# Core.net
KiCad netlist of a schematic drawn in Altium Designer
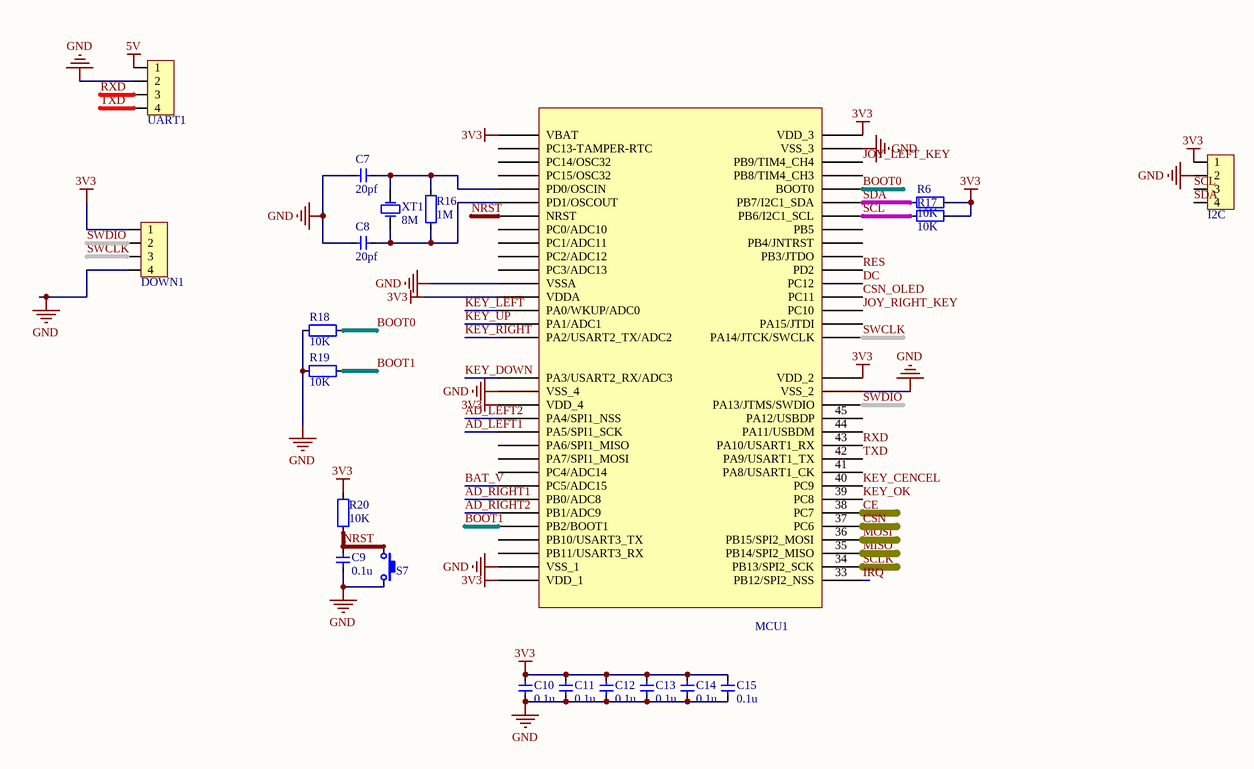
[diagram p0: Core.SchDoc]

(export (version "E")
  (design (tool "Eeschema 10.0.6"))
  (components
    (comp (ref "C7")
      (value "20pf")
      (footprint "PCB_PassiveCap:CAP_0603")
      (description "Capacitor")
      (fields (field (name "Comment") "Cap_0603"))
      (libsource (lib "SCH_Passive") (part "Cap_0603"))
    )
    (comp (ref "C8")
      (value "20pf")
      (footprint "PCB_PassiveCap:CAP_0603")
      (description "Capacitor")
      (fields (field (name "Comment") "Cap_0603"))
      (libsource (lib "SCH_Passive") (part "Cap_0603"))
    )
    (comp (ref "C9")
      (value "0.1u")
      (footprint "PCB_PassiveCap:CAP_0603")
      (description "Capacitor")
      (fields (field (name "Comment") "Cap_0603"))
      (libsource (lib "SCH_Passive") (part "Cap_0603"))
    )
    (comp (ref "C10")
      (value "0.1u")
      (footprint "PCB_PassiveCap:CAP_0603")
      (description "Capacitor")
      (fields (field (name "Comment") "Cap_0603"))
      (libsource (lib "SCH_Passive") (part "Cap_0603"))
    )
    (comp (ref "C11")
      (value "0.1u")
      (footprint "PCB_PassiveCap:CAP_0603")
      (description "Capacitor")
      (fields (field (name "Comment") "Cap_0603"))
      (libsource (lib "SCH_Passive") (part "Cap_0603"))
    )
    (comp (ref "C12")
      (value "0.1u")
      (footprint "PCB_PassiveCap:CAP_0603")
      (description "Capacitor")
      (fields (field (name "Comment") "Cap_0603"))
      (libsource (lib "SCH_Passive") (part "Cap_0603"))
    )
    (comp (ref "C13")
      (value "0.1u")
      (footprint "PCB_PassiveCap:CAP_0603")
      (description "Capacitor")
      (fields (field (name "Comment") "Cap_0603"))
      (libsource (lib "SCH_Passive") (part "Cap_0603"))
    )
    (comp (ref "C14")
      (value "0.1u")
      (footprint "PCB_PassiveCap:CAP_0603")
      (description "Capacitor")
      (fields (field (name "Comment") "Cap_0603"))
      (libsource (lib "SCH_Passive") (part "Cap_0603"))
    )
    (comp (ref "C15")
      (value "0.1u")
      (footprint "PCB_PassiveCap:CAP_0603")
      (description "Capacitor")
      (fields (field (name "Comment") "Cap_0603"))
      (libsource (lib "SCH_Passive") (part "Cap_0603"))
    )
    (comp (ref "DOWN1")
      (value "HDR1x4_2.54")
      (footprint "PCB_ConnectorHDR:HDR1x4_2.54_180")
      (description "Header")
      (libsource (lib "SCH_ConnectorHDR") (part "HDR1x4_2.54"))
    )
    (comp (ref "I2C")
      (value "HDR1x4_2.54")
      (footprint "PCB_ConnectorHDR:HDR1x4_2.54_180")
      (description "Header")
      (libsource (lib "SCH_ConnectorHDR") (part "HDR1x4_2.54"))
    )
    (comp (ref "MCU1")
      (value "STM32F103RC")
      (footprint "LQFP_P0.5_64")
      (description "MCU")
      (libsource (lib "SCH_IntegratedCircuit") (part "STM32F103RC"))
    )
    (comp (ref "R6")
      (value "10K")
      (footprint "PCB_PassiveRes:RES_0603")
      (description "Resistor")
      (fields (field (name "Comment") "Res_0603"))
      (libsource (lib "") (part "Res_0603_1"))
    )
    (comp (ref "R16")
      (value "1M")
      (footprint "PCB_PassiveRes:RES_0603")
      (description "Resistor")
      (fields (field (name "Comment") "Res_0603"))
      (libsource (lib "") (part "Res_0603_3"))
    )
    (comp (ref "R17")
      (value "10K")
      (footprint "PCB_PassiveRes:RES_0603")
      (description "Resistor")
      (fields (field (name "Comment") "Res_0603"))
      (libsource (lib "") (part "Res_0603_1"))
    )
    (comp (ref "R18")
      (value "10K")
      (footprint "PCB_PassiveRes:RES_0603")
      (description "Resistor")
      (fields (field (name "Comment") "Res_0603"))
      (libsource (lib "") (part "Res_0603_2"))
    )
    (comp (ref "R19")
      (value "10K")
      (footprint "PCB_PassiveRes:RES_0603")
      (description "Resistor")
      (fields (field (name "Comment") "Res_0603"))
      (libsource (lib "") (part "Res_0603_2"))
    )
    (comp (ref "R20")
      (value "10K")
      (footprint "PCB_PassiveRes:RES_0603")
      (description "Resistor")
      (fields (field (name "Comment") "Res_0603"))
      (libsource (lib "SCH_Passive") (part "Res_0603"))
    )
    (comp (ref "S7")
      (value "ButtonTACT_3x4x2_180")
      (footprint "PCB_Switch:ButtonTACT_3x4x2_180H")
      (description "Button")
      (libsource (lib "SCH_Switch") (part "ButtonTACT_3x4x2_180"))
    )
    (comp (ref "UART1")
      (value "HDR1x4_2.54")
      (footprint "PCB_ConnectorHDR:HDR1x4_2.54_180")
      (description "Header")
      (libsource (lib "SCH_ConnectorHDR") (part "HDR1x4_2.54"))
    )
    (comp (ref "XT1")
      (value "8M")
      (footprint "PCB_Oscillator:XT_5032_2")
      (description "Crystal Oscillator")
      (fields (field (name "Comment") "XTAL_5032_2P"))
      (libsource (lib "SCH_Oscillator") (part "XTAL_5032_2P"))
    )
  )
  (nets
    (net (code "1") (name "/AD_LEFT1") (class "Default")
      (node (ref "MCU1") (pin "21") (pinfunction "PA5/SPI1_SCK_21") (pintype "passive"))
    )
    (net (code "2") (name "/AD_LEFT2") (class "Default")
      (node (ref "MCU1") (pin "20") (pinfunction "PA4/SPI1_NSS_20") (pintype "passive"))
    )
    (net (code "3") (name "/AD_RIGHT1") (class "Default")
      (node (ref "MCU1") (pin "26") (pinfunction "PB0/ADC8_26") (pintype "passive"))
    )
    (net (code "4") (name "/AD_RIGHT2") (class "Default")
      (node (ref "MCU1") (pin "27") (pinfunction "PB1/ADC9_27") (pintype "passive"))
    )
    (net (code "5") (name "/BAT_V") (class "Default")
      (node (ref "MCU1") (pin "25") (pinfunction "PC5/ADC15_25") (pintype "passive"))
    )
    (net (code "6") (name "/BOOT0") (class "Default")
      (node (ref "MCU1") (pin "60") (pinfunction "BOOT0_60") (pintype "passive"))
      (node (ref "R18") (pin "1") (pinfunction "1_1") (pintype "passive"))
    )
    (net (code "7") (name "/BOOT1") (class "Default")
      (node (ref "MCU1") (pin "28") (pinfunction "PB2/BOOT1_28") (pintype "passive"))
      (node (ref "R19") (pin "1") (pinfunction "1_1") (pintype "passive"))
    )
    (net (code "8") (name "/CE") (class "Default")
      (node (ref "MCU1") (pin "38") (pinfunction "PC7_38") (pintype "passive"))
    )
    (net (code "9") (name "/CSN") (class "Default")
      (node (ref "MCU1") (pin "37") (pinfunction "PC6_37") (pintype "passive"))
    )
    (net (code "10") (name "/CSN_OLED") (class "Default")
      (node (ref "MCU1") (pin "52") (pinfunction "PC11_52") (pintype "passive"))
    )
    (net (code "11") (name "/DC") (class "Default")
      (node (ref "MCU1") (pin "53") (pinfunction "PC12_53") (pintype "passive"))
    )
    (net (code "12") (name "/IRQ") (class "Default")
      (node (ref "MCU1") (pin "33") (pinfunction "PB12/SPI2_NSS_33") (pintype "passive"))
    )
    (net (code "13") (name "/JOY_LEFT_KEY") (class "Default")
      (node (ref "MCU1") (pin "62") (pinfunction "PB9/TIM4_CH4_62") (pintype "passive"))
    )
    (net (code "14") (name "/JOY_RIGHT_KEY") (class "Default")
      (node (ref "MCU1") (pin "51") (pinfunction "PC10_51") (pintype "passive"))
    )
    (net (code "15") (name "/KEY_CENCEL") (class "Default")
      (node (ref "MCU1") (pin "40") (pinfunction "PC9_40") (pintype "passive"))
    )
    (net (code "16") (name "/KEY_DOWN") (class "Default")
      (node (ref "MCU1") (pin "17") (pinfunction "PA3/USART2_RX/ADC3_17") (pintype "passive"))
    )
    (net (code "17") (name "/KEY_LEFT") (class "Default")
      (node (ref "MCU1") (pin "14") (pinfunction "PA0/WKUP/ADC0_14") (pintype "passive"))
    )
    (net (code "18") (name "/KEY_OK") (class "Default")
      (node (ref "MCU1") (pin "39") (pinfunction "PC8_39") (pintype "passive"))
    )
    (net (code "19") (name "/KEY_RIGHT") (class "Default")
      (node (ref "MCU1") (pin "16") (pinfunction "PA2/USART2_TX/ADC2_16") (pintype "passive"))
    )
    (net (code "20") (name "/KEY_UP") (class "Default")
      (node (ref "MCU1") (pin "15") (pinfunction "PA1/ADC1_15") (pintype "passive"))
    )
    (net (code "21") (name "/MISO") (class "Default")
      (node (ref "MCU1") (pin "35") (pinfunction "PB14/SPI2_MISO_35") (pintype "passive"))
    )
    (net (code "22") (name "/MOSI") (class "Default")
      (node (ref "MCU1") (pin "36") (pinfunction "PB15/SPI2_MOSI_36") (pintype "passive"))
    )
    (net (code "23") (name "/NRST") (class "Default")
      (node (ref "C9") (pin "2") (pinfunction "2_2") (pintype "passive"))
      (node (ref "MCU1") (pin "7") (pinfunction "NRST_7") (pintype "passive"))
      (node (ref "R20") (pin "2") (pinfunction "2_2") (pintype "passive"))
      (node (ref "S7") (pin "1") (pinfunction "1_1") (pintype "passive"))
    )
    (net (code "24") (name "/RES") (class "Default")
      (node (ref "MCU1") (pin "54") (pinfunction "PD2_54") (pintype "passive"))
    )
    (net (code "25") (name "/RXD") (class "Default")
      (node (ref "MCU1") (pin "43") (pinfunction "PA10/USART1_RX_43") (pintype "passive"))
      (node (ref "UART1") (pin "3") (pinfunction "3_3") (pintype "passive"))
    )
    (net (code "26") (name "/SCL") (class "Default")
      (node (ref "I2C") (pin "3") (pinfunction "3_3") (pintype "passive"))
      (node (ref "MCU1") (pin "58") (pinfunction "PB6/I2C1_SCL_58") (pintype "passive"))
      (node (ref "R17") (pin "1") (pinfunction "1_1") (pintype "passive"))
    )
    (net (code "27") (name "/SCLK") (class "Default")
      (node (ref "MCU1") (pin "34") (pinfunction "PB13/SPI2_SCK_34") (pintype "passive"))
    )
    (net (code "28") (name "/SDA") (class "Default")
      (node (ref "I2C") (pin "4") (pinfunction "4_4") (pintype "passive"))
      (node (ref "MCU1") (pin "59") (pinfunction "PB7/I2C1_SDA_59") (pintype "passive"))
      (node (ref "R6") (pin "1") (pinfunction "1_1") (pintype "passive"))
    )
    (net (code "29") (name "/SWCLK") (class "Default")
      (node (ref "DOWN1") (pin "3") (pinfunction "3_3") (pintype "passive"))
      (node (ref "MCU1") (pin "49") (pinfunction "PA14/JTCK/SWCLK_49") (pintype "passive"))
    )
    (net (code "30") (name "/SWDIO") (class "Default")
      (node (ref "DOWN1") (pin "2") (pinfunction "2_2") (pintype "passive"))
      (node (ref "MCU1") (pin "46") (pinfunction "PA13/JTMS/SWDIO_46") (pintype "passive"))
    )
    (net (code "31") (name "/TXD") (class "Default")
      (node (ref "MCU1") (pin "42") (pinfunction "PA9/USART1_TX_42") (pintype "passive"))
      (node (ref "UART1") (pin "4") (pinfunction "4_4") (pintype "passive"))
    )
    (net (code "32") (name "3V3") (class "Default")
      (node (ref "C10") (pin "2") (pinfunction "2_2") (pintype "passive"))
      (node (ref "C11") (pin "2") (pinfunction "2_2") (pintype "passive"))
      (node (ref "C12") (pin "2") (pinfunction "2_2") (pintype "passive"))
      (node (ref "C13") (pin "2") (pinfunction "2_2") (pintype "passive"))
      (node (ref "C14") (pin "2") (pinfunction "2_2") (pintype "passive"))
      (node (ref "C15") (pin "2") (pinfunction "2_2") (pintype "passive"))
      (node (ref "DOWN1") (pin "1") (pinfunction "1_1") (pintype "passive"))
      (node (ref "I2C") (pin "1") (pinfunction "1_1") (pintype "passive"))
      (node (ref "MCU1") (pin "1") (pinfunction "VBAT_1") (pintype "passive"))
      (node (ref "MCU1") (pin "13") (pinfunction "VDDA_13") (pintype "passive"))
      (node (ref "MCU1") (pin "19") (pinfunction "VDD_4_19") (pintype "passive"))
      (node (ref "MCU1") (pin "32") (pinfunction "VDD_1_32") (pintype "passive"))
      (node (ref "MCU1") (pin "48") (pinfunction "VDD_2_48") (pintype "passive"))
      (node (ref "MCU1") (pin "64") (pinfunction "VDD_3_64") (pintype "passive"))
      (node (ref "R17") (pin "2") (pinfunction "2_2") (pintype "passive"))
      (node (ref "R20") (pin "1") (pinfunction "1_1") (pintype "passive"))
      (node (ref "R6") (pin "2") (pinfunction "2_2") (pintype "passive"))
    )
    (net (code "33") (name "5V") (class "Default")
      (node (ref "UART1") (pin "1") (pinfunction "1_1") (pintype "passive"))
    )
    (net (code "34") (name "GND") (class "Default")
      (node (ref "C10") (pin "1") (pinfunction "1_1") (pintype "passive"))
      (node (ref "C11") (pin "1") (pinfunction "1_1") (pintype "passive"))
      (node (ref "C12") (pin "1") (pinfunction "1_1") (pintype "passive"))
      (node (ref "C13") (pin "1") (pinfunction "1_1") (pintype "passive"))
      (node (ref "C14") (pin "1") (pinfunction "1_1") (pintype "passive"))
      (node (ref "C15") (pin "1") (pinfunction "1_1") (pintype "passive"))
      (node (ref "C7") (pin "1") (pinfunction "1_1") (pintype "passive"))
      (node (ref "C8") (pin "1") (pinfunction "1_1") (pintype "passive"))
      (node (ref "C9") (pin "1") (pinfunction "1_1") (pintype "passive"))
      (node (ref "DOWN1") (pin "4") (pinfunction "4_4") (pintype "passive"))
      (node (ref "I2C") (pin "2") (pinfunction "2_2") (pintype "passive"))
      (node (ref "MCU1") (pin "12") (pinfunction "VSSA_12") (pintype "passive"))
      (node (ref "MCU1") (pin "18") (pinfunction "VSS_4_18") (pintype "passive"))
      (node (ref "MCU1") (pin "31") (pinfunction "VSS_1_31") (pintype "passive"))
      (node (ref "MCU1") (pin "47") (pinfunction "VSS_2_47") (pintype "passive"))
      (node (ref "MCU1") (pin "63") (pinfunction "VSS_3_63") (pintype "passive"))
      (node (ref "R18") (pin "2") (pinfunction "2_2") (pintype "passive"))
      (node (ref "R19") (pin "2") (pinfunction "2_2") (pintype "passive"))
      (node (ref "S7") (pin "2") (pinfunction "2_2") (pintype "passive"))
      (node (ref "UART1") (pin "2") (pinfunction "2_2") (pintype "passive"))
    )
    (net (code "35") (name "Net-(MCU1-PD0{slash}OSCIN)") (class "Default")
      (node (ref "C7") (pin "2") (pinfunction "2_2") (pintype "passive"))
      (node (ref "MCU1") (pin "5") (pinfunction "PD0/OSCIN_5") (pintype "passive"))
      (node (ref "R16") (pin "2") (pinfunction "2_2") (pintype "passive"))
      (node (ref "XT1") (pin "2") (pinfunction "OSC2_2") (pintype "passive"))
    )
    (net (code "36") (name "Net-(MCU1-PD1{slash}OSCOUT)") (class "Default")
      (node (ref "C8") (pin "2") (pinfunction "2_2") (pintype "passive"))
      (node (ref "MCU1") (pin "6") (pinfunction "PD1/OSCOUT_6") (pintype "passive"))
      (node (ref "R16") (pin "1") (pinfunction "1_1") (pintype "passive"))
      (node (ref "XT1") (pin "1") (pinfunction "OSC1_1") (pintype "passive"))
    )
    (net (code "37") (name "unconnected-(MCU1-PA6{slash}SPI1_MISO-Pad22)") (class "Default")
      (node (ref "MCU1") (pin "22") (pinfunction "PA6/SPI1_MISO_22") (pintype "passive"))
    )
    (net (code "38") (name "unconnected-(MCU1-PA7{slash}SPI1_MOSI-Pad23)") (class "Default")
      (node (ref "MCU1") (pin "23") (pinfunction "PA7/SPI1_MOSI_23") (pintype "passive"))
    )
    (net (code "39") (name "unconnected-(MCU1-PA8{slash}USART1_CK-Pad41)") (class "Default")
      (node (ref "MCU1") (pin "41") (pinfunction "PA8/USART1_CK_41") (pintype "passive"))
    )
    (net (code "40") (name "unconnected-(MCU1-PA11{slash}USBDM-Pad44)") (class "Default")
      (node (ref "MCU1") (pin "44") (pinfunction "PA11/USBDM_44") (pintype "passive"))
    )
    (net (code "41") (name "unconnected-(MCU1-PA12{slash}USBDP-Pad45)") (class "Default")
      (node (ref "MCU1") (pin "45") (pinfunction "PA12/USBDP_45") (pintype "passive"))
    )
    (net (code "42") (name "unconnected-(MCU1-PA15{slash}JTDI-Pad50)") (class "Default")
      (node (ref "MCU1") (pin "50") (pinfunction "PA15/JTDI_50") (pintype "passive"))
    )
    (net (code "43") (name "unconnected-(MCU1-PB3{slash}JTDO-Pad55)") (class "Default")
      (node (ref "MCU1") (pin "55") (pinfunction "PB3/JTDO_55") (pintype "passive"))
    )
    (net (code "44") (name "unconnected-(MCU1-PB4{slash}JNTRST-Pad56)") (class "Default")
      (node (ref "MCU1") (pin "56") (pinfunction "PB4/JNTRST_56") (pintype "passive"))
    )
    (net (code "45") (name "unconnected-(MCU1-PB5-Pad57)") (class "Default")
      (node (ref "MCU1") (pin "57") (pinfunction "PB5_57") (pintype "passive"))
    )
    (net (code "46") (name "unconnected-(MCU1-PB8{slash}TIM4_CH3-Pad61)") (class "Default")
      (node (ref "MCU1") (pin "61") (pinfunction "PB8/TIM4_CH3_61") (pintype "passive"))
    )
    (net (code "47") (name "unconnected-(MCU1-PB10{slash}USART3_TX-Pad29)") (class "Default")
      (node (ref "MCU1") (pin "29") (pinfunction "PB10/USART3_TX_29") (pintype "passive"))
    )
    (net (code "48") (name "unconnected-(MCU1-PB11{slash}USART3_RX-Pad30)") (class "Default")
      (node (ref "MCU1") (pin "30") (pinfunction "PB11/USART3_RX_30") (pintype "passive"))
    )
    (net (code "49") (name "unconnected-(MCU1-PC0{slash}ADC10-Pad8)") (class "Default")
      (node (ref "MCU1") (pin "8") (pinfunction "PC0/ADC10_8") (pintype "passive"))
    )
    (net (code "50") (name "unconnected-(MCU1-PC1{slash}ADC11-Pad9)") (class "Default")
      (node (ref "MCU1") (pin "9") (pinfunction "PC1/ADC11_9") (pintype "passive"))
    )
    (net (code "51") (name "unconnected-(MCU1-PC2{slash}ADC12-Pad10)") (class "Default")
      (node (ref "MCU1") (pin "10") (pinfunction "PC2/ADC12_10") (pintype "passive"))
    )
    (net (code "52") (name "unconnected-(MCU1-PC3{slash}ADC13-Pad11)") (class "Default")
      (node (ref "MCU1") (pin "11") (pinfunction "PC3/ADC13_11") (pintype "passive"))
    )
    (net (code "53") (name "unconnected-(MCU1-PC4{slash}ADC14-Pad24)") (class "Default")
      (node (ref "MCU1") (pin "24") (pinfunction "PC4/ADC14_24") (pintype "passive"))
    )
    (net (code "54") (name "unconnected-(MCU1-PC13-TAMPER-RTC-Pad2)") (class "Default")
      (node (ref "MCU1") (pin "2") (pinfunction "PC13-TAMPER-RTC_2") (pintype "passive"))
    )
    (net (code "55") (name "unconnected-(MCU1-PC14{slash}OSC32-Pad3)") (class "Default")
      (node (ref "MCU1") (pin "3") (pinfunction "PC14/OSC32_3") (pintype "passive"))
    )
    (net (code "56") (name "unconnected-(MCU1-PC15{slash}OSC32-Pad4)") (class "Default")
      (node (ref "MCU1") (pin "4") (pinfunction "PC15/OSC32_4") (pintype "passive"))
    )
  )
)
